# 05_LMS1_Misc.net
KiCad netlist of a schematic drawn in Altium Designer
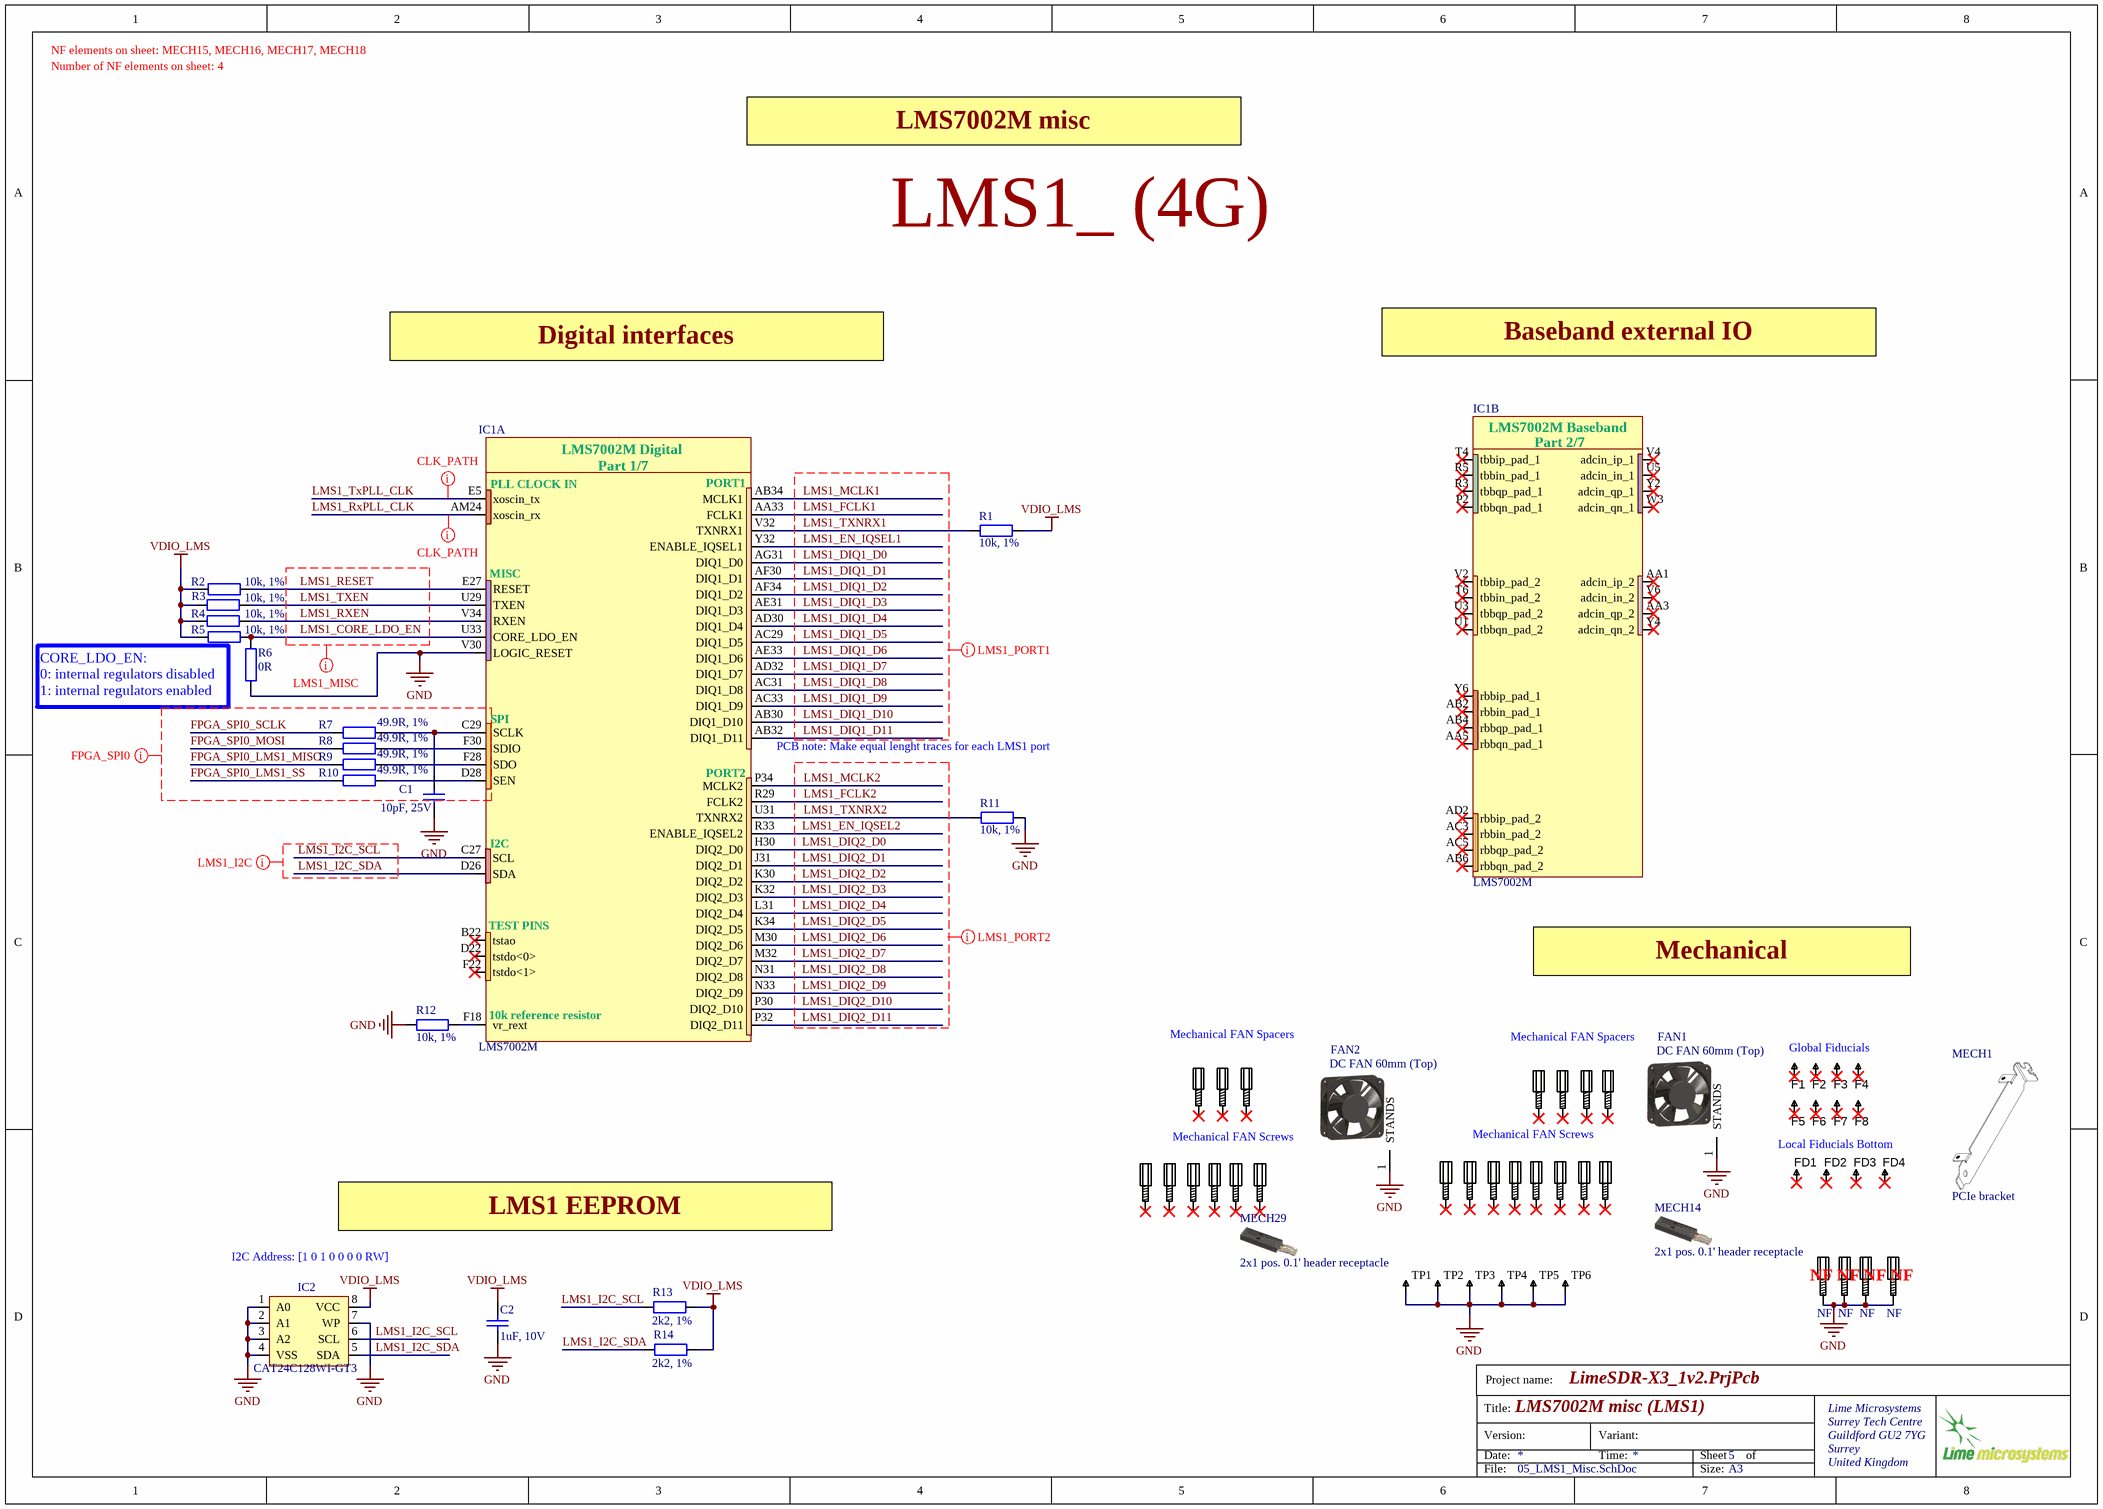
[diagram p0: 05_LMS1_Misc.SchDoc]

(export (version "E")
  (design (tool "Eeschema 10.0.6"))
  (components
    (comp (ref "C1")
      (value "10pF, 25V")
      (footprint "CAP0402")
      (fields (field (name "MANUFACTURER") "AVX"))
      (libsource (lib "LimeMicroAltiumLib_schLib") (part "Cap_0402"))
    )
    (comp (ref "C2")
      (value "1uF, 10V")
      (footprint "CAP0402")
      (fields (field (name "MANUFACTURER") "TDK"))
      (libsource (lib "") (part "Cap_0402_1"))
    )
    (comp (ref "F1")
      (value "Fiducial")
      (footprint "Fiducial")
      (libsource (lib "VGTU_Altium_lib") (part "Fiducial"))
    )
    (comp (ref "F2")
      (value "Fiducial")
      (footprint "Fiducial")
      (libsource (lib "VGTU_Altium_lib") (part "Fiducial"))
    )
    (comp (ref "F3")
      (value "Fiducial")
      (footprint "Fiducial")
      (libsource (lib "VGTU_Altium_lib") (part "Fiducial"))
    )
    (comp (ref "F4")
      (value "Fiducial")
      (footprint "Fiducial")
      (libsource (lib "VGTU_Altium_lib") (part "Fiducial"))
    )
    (comp (ref "F5")
      (value "Fiducial")
      (footprint "Fiducial")
      (libsource (lib "VGTU_Altium_lib") (part "Fiducial"))
    )
    (comp (ref "F6")
      (value "Fiducial")
      (footprint "Fiducial")
      (libsource (lib "VGTU_Altium_lib") (part "Fiducial"))
    )
    (comp (ref "F7")
      (value "Fiducial")
      (footprint "Fiducial")
      (libsource (lib "VGTU_Altium_lib") (part "Fiducial"))
    )
    (comp (ref "F8")
      (value "Fiducial")
      (footprint "Fiducial")
      (libsource (lib "VGTU_Altium_lib") (part "Fiducial"))
    )
    (comp (ref "FAN1")
      (value "DC FAN 60mm (Top)")
      (footprint "FAN_60mm")
      (fields (field (name "MANUFACTURER") "Sunon"))
      (libsource (lib "LimeMicroAltiumLib_schLib") (part "12V_DC_FAN"))
    )
    (comp (ref "FAN2")
      (value "DC FAN 60mm (Top)")
      (footprint "FAN_60mm")
      (fields (field (name "MANUFACTURER") "Sunon"))
      (libsource (lib "LimeMicroAltiumLib_schLib") (part "12V_DC_FAN"))
    )
    (comp (ref "FD1")
      (value "Fiducial")
      (footprint "Fiducial_local")
      (libsource (lib "") (part "Fiducial_1"))
    )
    (comp (ref "FD2")
      (value "Fiducial")
      (footprint "Fiducial_local")
      (libsource (lib "LimeMicroAltiumLib_schLib") (part "Fiducial"))
    )
    (comp (ref "FD3")
      (value "Fiducial")
      (footprint "Fiducial_local")
      (libsource (lib "") (part "Fiducial_2"))
    )
    (comp (ref "FD4")
      (value "Fiducial")
      (footprint "Fiducial_local")
      (libsource (lib "LimeMicroAltiumLib_schLib") (part "Fiducial"))
    )
    (comp (ref "IC1")
      (value "LMS7002M")
      (footprint "LMS7002M_v5")
      (description "Schematic symbol revision 4. Default footprint - 0.31mm pad")
      (fields (field (name "MANUFACTURER") "Lime Microsystems"))
      (libsource (lib "LimeMicroAltiumLib_schLib_r04") (part "LMS7002Mr4"))
    )
    (comp (ref "IC2")
      (value "CAT24C128WI-GT3")
      (footprint "SOIC127P600-8DL_v2")
      (fields (field (name "MANUFACTURER") "ON Semiconductor") (field (name "BASE PART NUMBER") "CAT24C128"))
      (libsource (lib "LimeMicroAltiumLib_schLib") (part "24FC64F"))
    )
    (comp (ref "MECH1")
      (value "PCIe bracket")
      (footprint "PCIe_bracket")
      (fields (field (name "MANUFACTURER") "Keystone Electronics"))
      (libsource (lib "LimeMicroAltiumLib_schLib_r01") (part "PCIe_bracket"))
    )
    (comp (ref "MECH2")
      (value "Spacer M3")
      (description "STANDOFF M/F MET 5MM HEX 10MM L")
      (fields (field (name "MANUFACTURER") "BOSSARD"))
      (libsource (lib "LimeMicroAltiumLib_schLib") (part "STANDOFF_M-F_THREADED_M3x8x10mm_HEX_5mm dia"))
    )
    (comp (ref "MECH3")
      (value "Spacer M3")
      (description "STANDOFF M/F MET 5MM HEX 10MM L")
      (fields (field (name "MANUFACTURER") "BOSSARD"))
      (libsource (lib "LimeMicroAltiumLib_schLib") (part "STANDOFF_M-F_THREADED_M3x8x10mm_HEX_5mm dia"))
    )
    (comp (ref "MECH4")
      (value "Spacer M3")
      (description "STANDOFF M/F MET 5MM HEX 10MM L")
      (fields (field (name "MANUFACTURER") "BOSSARD"))
      (libsource (lib "LimeMicroAltiumLib_schLib") (part "STANDOFF_M-F_THREADED_M3x8x10mm_HEX_5mm dia"))
    )
    (comp (ref "MECH5")
      (value "Spacer M3")
      (description "STANDOFF M/F MET 5MM HEX 10MM L")
      (fields (field (name "MANUFACTURER") "BOSSARD"))
      (libsource (lib "LimeMicroAltiumLib_schLib") (part "STANDOFF_M-F_THREADED_M3x8x10mm_HEX_5mm dia"))
    )
    (comp (ref "MECH6")
      (value "Screws M3")
      (description "STANDOFF M/F MET 5MM HEX 10MM L")
      (fields (field (name "MANUFACTURER") "BOSSARD"))
      (libsource (lib "") (part "STANDOFF_M-F_THREADED_M3x8x10mm_HEX_5mm dia_1"))
    )
    (comp (ref "MECH7")
      (value "Screws M3")
      (description "STANDOFF M/F MET 5MM HEX 10MM L")
      (fields (field (name "MANUFACTURER") "BOSSARD"))
      (libsource (lib "") (part "STANDOFF_M-F_THREADED_M3x8x10mm_HEX_5mm dia_1"))
    )
    (comp (ref "MECH8")
      (value "Screws M3")
      (description "STANDOFF M/F MET 5MM HEX 10MM L")
      (fields (field (name "MANUFACTURER") "BOSSARD"))
      (libsource (lib "") (part "STANDOFF_M-F_THREADED_M3x8x10mm_HEX_5mm dia_1"))
    )
    (comp (ref "MECH9")
      (value "Screws M3")
      (description "STANDOFF M/F MET 5MM HEX 10MM L")
      (fields (field (name "MANUFACTURER") "BOSSARD"))
      (libsource (lib "") (part "STANDOFF_M-F_THREADED_M3x8x10mm_HEX_5mm dia_1"))
    )
    (comp (ref "MECH10")
      (value "Screws M3")
      (description "STANDOFF M/F MET 5MM HEX 10MM L")
      (fields (field (name "MANUFACTURER") "BOSSARD"))
      (libsource (lib "") (part "STANDOFF_M-F_THREADED_M3x8x10mm_HEX_5mm dia_1"))
    )
    (comp (ref "MECH11")
      (value "Screws M3")
      (description "STANDOFF M/F MET 5MM HEX 10MM L")
      (fields (field (name "MANUFACTURER") "BOSSARD"))
      (libsource (lib "") (part "STANDOFF_M-F_THREADED_M3x8x10mm_HEX_5mm dia_1"))
    )
    (comp (ref "MECH12")
      (value "Screws M3")
      (description "STANDOFF M/F MET 5MM HEX 10MM L")
      (fields (field (name "MANUFACTURER") "BOSSARD"))
      (libsource (lib "") (part "STANDOFF_M-F_THREADED_M3x8x10mm_HEX_5mm dia_1"))
    )
    (comp (ref "MECH13")
      (value "Screws M3")
      (description "STANDOFF M/F MET 5MM HEX 10MM L")
      (fields (field (name "MANUFACTURER") "BOSSARD"))
      (libsource (lib "") (part "STANDOFF_M-F_THREADED_M3x8x10mm_HEX_5mm dia_1"))
    )
    (comp (ref "MECH14")
      (value "2x1 pos. 0.1' header receptacle")
      (fields (field (name "MANUFACTURER") "Molex"))
      (libsource (lib "LimeMicroAltiumLib_schLib_r01") (part "Header_1x2_receptacle"))
    )
    (comp (ref "MECH15")
      (value "Standoff")
      (footprint "PCB_standoff")
      (description "STANDOFF M/F MET 5MM HEX 10MM L")
      (fields (field (name "MANUFACTURER") "FIX&FASTEN") (field (name "ASSEMBLY INFO") "NF"))
      (libsource (lib "") (part "STANDOFF_M-F_THREADED_M3x8x10mm_HEX_5mm dia_1"))
    )
    (comp (ref "MECH16")
      (value "Standoff")
      (footprint "PCB_standoff")
      (description "STANDOFF M/F MET 5MM HEX 10MM L")
      (fields (field (name "MANUFACTURER") "FIX&FASTEN") (field (name "ASSEMBLY INFO") "NF"))
      (libsource (lib "") (part "STANDOFF_M-F_THREADED_M3x8x10mm_HEX_5mm dia_1"))
    )
    (comp (ref "MECH17")
      (value "Standoff")
      (footprint "PCB_standoff")
      (description "STANDOFF M/F MET 5MM HEX 10MM L")
      (fields (field (name "MANUFACTURER") "FIX&FASTEN") (field (name "ASSEMBLY INFO") "NF"))
      (libsource (lib "") (part "STANDOFF_M-F_THREADED_M3x8x10mm_HEX_5mm dia_1"))
    )
    (comp (ref "MECH18")
      (value "Standoff")
      (footprint "PCB_standoff")
      (description "STANDOFF M/F MET 5MM HEX 10MM L")
      (fields (field (name "MANUFACTURER") "FIX&FASTEN") (field (name "ASSEMBLY INFO") "NF"))
      (libsource (lib "") (part "STANDOFF_M-F_THREADED_M3x8x10mm_HEX_5mm dia_2"))
    )
    (comp (ref "MECH20")
      (value "Spacer M3")
      (description "STANDOFF M/F MET 5MM HEX 10MM L")
      (fields (field (name "MANUFACTURER") "BOSSARD"))
      (libsource (lib "LimeMicroAltiumLib_schLib") (part "STANDOFF_M-F_THREADED_M3x8x10mm_HEX_5mm dia"))
    )
    (comp (ref "MECH21")
      (value "Spacer M3")
      (description "STANDOFF M/F MET 5MM HEX 10MM L")
      (fields (field (name "MANUFACTURER") "BOSSARD"))
      (libsource (lib "LimeMicroAltiumLib_schLib") (part "STANDOFF_M-F_THREADED_M3x8x10mm_HEX_5mm dia"))
    )
    (comp (ref "MECH22")
      (value "Spacer M3")
      (description "STANDOFF M/F MET 5MM HEX 10MM L")
      (fields (field (name "MANUFACTURER") "BOSSARD"))
      (libsource (lib "LimeMicroAltiumLib_schLib") (part "STANDOFF_M-F_THREADED_M3x8x10mm_HEX_5mm dia"))
    )
    (comp (ref "MECH23")
      (value "Screws M3")
      (description "STANDOFF M/F MET 5MM HEX 10MM L")
      (fields (field (name "MANUFACTURER") "BOSSARD"))
      (libsource (lib "") (part "STANDOFF_M-F_THREADED_M3x8x10mm_HEX_5mm dia_1"))
    )
    (comp (ref "MECH24")
      (value "Screws M3")
      (description "STANDOFF M/F MET 5MM HEX 10MM L")
      (fields (field (name "MANUFACTURER") "BOSSARD"))
      (libsource (lib "") (part "STANDOFF_M-F_THREADED_M3x8x10mm_HEX_5mm dia_1"))
    )
    (comp (ref "MECH25")
      (value "Screws M3")
      (description "STANDOFF M/F MET 5MM HEX 10MM L")
      (fields (field (name "MANUFACTURER") "BOSSARD"))
      (libsource (lib "") (part "STANDOFF_M-F_THREADED_M3x8x10mm_HEX_5mm dia_1"))
    )
    (comp (ref "MECH26")
      (value "Screws M3")
      (description "STANDOFF M/F MET 5MM HEX 10MM L")
      (fields (field (name "MANUFACTURER") "BOSSARD"))
      (libsource (lib "") (part "STANDOFF_M-F_THREADED_M3x8x10mm_HEX_5mm dia_1"))
    )
    (comp (ref "MECH27")
      (value "Screws M3")
      (description "STANDOFF M/F MET 5MM HEX 10MM L")
      (fields (field (name "MANUFACTURER") "BOSSARD"))
      (libsource (lib "") (part "STANDOFF_M-F_THREADED_M3x8x10mm_HEX_5mm dia_1"))
    )
    (comp (ref "MECH28")
      (value "Screws M3")
      (description "STANDOFF M/F MET 5MM HEX 10MM L")
      (fields (field (name "MANUFACTURER") "BOSSARD"))
      (libsource (lib "") (part "STANDOFF_M-F_THREADED_M3x8x10mm_HEX_5mm dia_1"))
    )
    (comp (ref "MECH29")
      (value "2x1 pos. 0.1' header receptacle")
      (fields (field (name "MANUFACTURER") "Molex"))
      (libsource (lib "LimeMicroAltiumLib_schLib_r01") (part "Header_1x2_receptacle"))
    )
    (comp (ref "R1")
      (value "10k, 1%")
      (footprint "RES0402")
      (fields (field (name "MANUFACTURER") "Yageo") (field (name "TOLERANCE") "±1%"))
      (libsource (lib "LimeMicroAltiumLib_schLib") (part "Res_0402"))
    )
    (comp (ref "R2")
      (value "10k, 1%")
      (footprint "RES0402")
      (fields (field (name "MANUFACTURER") "Yageo") (field (name "TOLERANCE") "±1%"))
      (libsource (lib "LimeMicroAltiumLib_schLib") (part "Res_0402"))
    )
    (comp (ref "R3")
      (value "10k, 1%")
      (footprint "RES0402")
      (fields (field (name "MANUFACTURER") "Yageo") (field (name "TOLERANCE") "±1%"))
      (libsource (lib "LimeMicroAltiumLib_schLib") (part "Res_0402"))
    )
    (comp (ref "R4")
      (value "10k, 1%")
      (footprint "RES0402")
      (fields (field (name "MANUFACTURER") "Yageo") (field (name "TOLERANCE") "±1%"))
      (libsource (lib "LimeMicroAltiumLib_schLib") (part "Res_0402"))
    )
    (comp (ref "R5")
      (value "10k, 1%")
      (footprint "RES0402")
      (fields (field (name "MANUFACTURER") "Yageo") (field (name "TOLERANCE") "±1%"))
      (libsource (lib "LimeMicroAltiumLib_schLib") (part "Res_0402"))
    )
    (comp (ref "R6")
      (value "0R")
      (footprint "RES0402")
      (fields (field (name "MANUFACTURER") "Yageo") (field (name "TOLERANCE") "Jumper"))
      (libsource (lib "LimeMicroAltiumLib_schLib") (part "Res_0402"))
    )
    (comp (ref "R7")
      (value "49.9R, 1%")
      (footprint "RES0402")
      (fields
        (field (name "TOLERANCE") "±1%")
        (field (name "MANUFACTURER") "Samsung Electro-Mechanics America, Inc.")
        (field (name "MANUFACTURER PART NUMBER") "RC1005F49R9CS")
      )
      (libsource (lib "LimeMicroAltiumLib_schLib") (part "Res_0402"))
    )
    (comp (ref "R8")
      (value "49.9R, 1%")
      (footprint "RES0402")
      (fields
        (field (name "TOLERANCE") "±1%")
        (field (name "MANUFACTURER") "Samsung Electro-Mechanics America, Inc.")
        (field (name "MANUFACTURER PART NUMBER") "RC1005F49R9CS")
      )
      (libsource (lib "LimeMicroAltiumLib_schLib") (part "Res_0402"))
    )
    (comp (ref "R9")
      (value "49.9R, 1%")
      (footprint "RES0402")
      (fields
        (field (name "TOLERANCE") "±1%")
        (field (name "MANUFACTURER") "Samsung Electro-Mechanics America, Inc.")
        (field (name "MANUFACTURER PART NUMBER") "RC1005F49R9CS")
      )
      (libsource (lib "LimeMicroAltiumLib_schLib") (part "Res_0402"))
    )
    (comp (ref "R10")
      (value "49.9R, 1%")
      (footprint "RES0402")
      (fields
        (field (name "TOLERANCE") "±1%")
        (field (name "MANUFACTURER") "Samsung Electro-Mechanics America, Inc.")
        (field (name "MANUFACTURER PART NUMBER") "RC1005F49R9CS")
      )
      (libsource (lib "LimeMicroAltiumLib_schLib") (part "Res_0402"))
    )
    (comp (ref "R11")
      (value "10k, 1%")
      (footprint "RES0402")
      (fields (field (name "MANUFACTURER") "Yageo") (field (name "TOLERANCE") "±1%"))
      (libsource (lib "LimeMicroAltiumLib_schLib") (part "Res_0402"))
    )
    (comp (ref "R12")
      (value "10k, 1%")
      (footprint "RES0402")
      (fields (field (name "MANUFACTURER") "Yageo") (field (name "TOLERANCE") "±1%"))
      (libsource (lib "") (part "Res_0402_1"))
    )
    (comp (ref "R13")
      (value "2k2, 1%")
      (footprint "RES0402")
      (fields (field (name "MANUFACTURER") "Stackpole Electronics Inc") (field (name "TOLERANCE") "±1%"))
      (libsource (lib "LimeMicroAltiumLib_schLib") (part "Res_0402"))
    )
    (comp (ref "R14")
      (value "2k2, 1%")
      (footprint "RES0402")
      (fields (field (name "MANUFACTURER") "Stackpole Electronics Inc") (field (name "TOLERANCE") "±1%"))
      (libsource (lib "LimeMicroAltiumLib_schLib") (part "Res_0402"))
    )
    (comp (ref "TP1")
      (value "TESTPOINT_THT_MINI")
      (footprint "TP-SMD-LOW_PROFILE")
      (description "Test Point PCB mount Miniature White")
      (fields (field (name "MANUFACTURER") "Harwin Inc"))
      (libsource (lib "LimeMicroAltiumLib_schLib") (part "TESTPOINT_THT_MINI"))
    )
    (comp (ref "TP2")
      (value "TESTPOINT_THT_MINI")
      (footprint "TP-SMD-LOW_PROFILE")
      (description "Test Point PCB mount Miniature White")
      (fields (field (name "MANUFACTURER") "Harwin Inc"))
      (libsource (lib "LimeMicroAltiumLib_schLib") (part "TESTPOINT_THT_MINI"))
    )
    (comp (ref "TP3")
      (value "TESTPOINT_THT_MINI")
      (footprint "TP-SMD-LOW_PROFILE")
      (description "Test Point PCB mount Miniature White")
      (fields (field (name "MANUFACTURER") "Harwin Inc"))
      (libsource (lib "LimeMicroAltiumLib_schLib") (part "TESTPOINT_THT_MINI"))
    )
    (comp (ref "TP4")
      (value "TESTPOINT_THT_MINI")
      (footprint "TP-SMD-LOW_PROFILE")
      (description "Test Point PCB mount Miniature White")
      (fields (field (name "MANUFACTURER") "Harwin Inc"))
      (libsource (lib "LimeMicroAltiumLib_schLib") (part "TESTPOINT_THT_MINI"))
    )
    (comp (ref "TP5")
      (value "TESTPOINT_THT_MINI")
      (footprint "TP-SMD-LOW_PROFILE")
      (description "Test Point PCB mount Miniature White")
      (fields (field (name "MANUFACTURER") "Harwin Inc"))
      (libsource (lib "LimeMicroAltiumLib_schLib") (part "TESTPOINT_THT_MINI"))
    )
    (comp (ref "TP6")
      (value "TESTPOINT_THT_MINI")
      (footprint "TP-SMD-LOW_PROFILE")
      (description "Test Point PCB mount Miniature White")
      (fields (field (name "MANUFACTURER") "Harwin Inc"))
      (libsource (lib "LimeMicroAltiumLib_schLib") (part "TESTPOINT_THT_MINI"))
    )
  )
  (nets
    (net (code "1") (name "/FPGA_SPI0_LMS1_MISO") (class "Default")
      (node (ref "R9") (pin "2") (pinfunction "2_2") (pintype "passive"))
    )
    (net (code "2") (name "/FPGA_SPI0_LMS1_SS") (class "Default")
      (node (ref "R10") (pin "2") (pinfunction "2_2") (pintype "passive"))
    )
    (net (code "3") (name "/FPGA_SPI0_MOSI") (class "Default")
      (node (ref "R8") (pin "2") (pinfunction "2_2") (pintype "passive"))
    )
    (net (code "4") (name "/FPGA_SPI0_SCLK") (class "Default")
      (node (ref "R7") (pin "2") (pinfunction "2_2") (pintype "passive"))
    )
    (net (code "5") (name "/LMS1_CORE_LDO_EN") (class "Default")
      (node (ref "IC1") (pin "U33") (pinfunction "CORE_LDO_EN_U33") (pintype "passive"))
      (node (ref "R5") (pin "1") (pinfunction "1_1") (pintype "passive"))
      (node (ref "R6") (pin "2") (pinfunction "2_2") (pintype "passive"))
    )
    (net (code "6") (name "/LMS1_DIQ1_D0") (class "Default")
      (node (ref "IC1") (pin "AG31") (pinfunction "DIQ1_D0_AG31") (pintype "passive"))
    )
    (net (code "7") (name "/LMS1_DIQ1_D1") (class "Default")
      (node (ref "IC1") (pin "AF30") (pinfunction "DIQ1_D1_AF30") (pintype "passive"))
    )
    (net (code "8") (name "/LMS1_DIQ1_D2") (class "Default")
      (node (ref "IC1") (pin "AF34") (pinfunction "DIQ1_D2_AF34") (pintype "passive"))
    )
    (net (code "9") (name "/LMS1_DIQ1_D3") (class "Default")
      (node (ref "IC1") (pin "AE31") (pinfunction "DIQ1_D3_AE31") (pintype "passive"))
    )
    (net (code "10") (name "/LMS1_DIQ1_D4") (class "Default")
      (node (ref "IC1") (pin "AD30") (pinfunction "DIQ1_D4_AD30") (pintype "passive"))
    )
    (net (code "11") (name "/LMS1_DIQ1_D5") (class "Default")
      (node (ref "IC1") (pin "AC29") (pinfunction "DIQ1_D5_AC29") (pintype "passive"))
    )
    (net (code "12") (name "/LMS1_DIQ1_D6") (class "Default")
      (node (ref "IC1") (pin "AE33") (pinfunction "DIQ1_D6_AE33") (pintype "passive"))
    )
    (net (code "13") (name "/LMS1_DIQ1_D7") (class "Default")
      (node (ref "IC1") (pin "AD32") (pinfunction "DIQ1_D7_AD32") (pintype "passive"))
    )
    (net (code "14") (name "/LMS1_DIQ1_D8") (class "Default")
      (node (ref "IC1") (pin "AC31") (pinfunction "DIQ1_D8_AC31") (pintype "passive"))
    )
    (net (code "15") (name "/LMS1_DIQ1_D9") (class "Default")
      (node (ref "IC1") (pin "AC33") (pinfunction "DIQ1_D9_AC33") (pintype "passive"))
    )
    (net (code "16") (name "/LMS1_DIQ1_D10") (class "Default")
      (node (ref "IC1") (pin "AB30") (pinfunction "DIQ1_D10_AB30") (pintype "passive"))
    )
    (net (code "17") (name "/LMS1_DIQ1_D11") (class "Default")
      (node (ref "IC1") (pin "AB32") (pinfunction "DIQ1_D11_AB32") (pintype "passive"))
    )
    (net (code "18") (name "/LMS1_DIQ2_D0") (class "Default")
      (node (ref "IC1") (pin "H30") (pinfunction "DIQ2_D0_H30") (pintype "passive"))
    )
    (net (code "19") (name "/LMS1_DIQ2_D1") (class "Default")
      (node (ref "IC1") (pin "J31") (pinfunction "DIQ2_D1_J31") (pintype "passive"))
    )
    (net (code "20") (name "/LMS1_DIQ2_D2") (class "Default")
      (node (ref "IC1") (pin "K30") (pinfunction "DIQ2_D2_K30") (pintype "passive"))
    )
    (net (code "21") (name "/LMS1_DIQ2_D3") (class "Default")
      (node (ref "IC1") (pin "K32") (pinfunction "DIQ2_D3_K32") (pintype "passive"))
    )
    (net (code "22") (name "/LMS1_DIQ2_D4") (class "Default")
      (node (ref "IC1") (pin "L31") (pinfunction "DIQ2_D4_L31") (pintype "passive"))
    )
    (net (code "23") (name "/LMS1_DIQ2_D5") (class "Default")
      (node (ref "IC1") (pin "K34") (pinfunction "DIQ2_D5_K34") (pintype "passive"))
    )
    (net (code "24") (name "/LMS1_DIQ2_D6") (class "Default")
      (node (ref "IC1") (pin "M30") (pinfunction "DIQ2_D6_M30") (pintype "passive"))
    )
    (net (code "25") (name "/LMS1_DIQ2_D7") (class "Default")
      (node (ref "IC1") (pin "M32") (pinfunction "DIQ2_D7_M32") (pintype "passive"))
    )
    (net (code "26") (name "/LMS1_DIQ2_D8") (class "Default")
      (node (ref "IC1") (pin "N31") (pinfunction "DIQ2_D8_N31") (pintype "passive"))
    )
    (net (code "27") (name "/LMS1_DIQ2_D9") (class "Default")
      (node (ref "IC1") (pin "N33") (pinfunction "DIQ2_D9_N33") (pintype "passive"))
    )
    (net (code "28") (name "/LMS1_DIQ2_D10") (class "Default")
      (node (ref "IC1") (pin "P30") (pinfunction "DIQ2_D10_P30") (pintype "passive"))
    )
    (net (code "29") (name "/LMS1_DIQ2_D11") (class "Default")
      (node (ref "IC1") (pin "P32") (pinfunction "DIQ2_D11_P32") (pintype "passive"))
    )
    (net (code "30") (name "/LMS1_EN_IQSEL1") (class "Default")
      (node (ref "IC1") (pin "Y32") (pinfunction "ENABLE_IQSEL1_Y32") (pintype "passive"))
    )
    (net (code "31") (name "/LMS1_EN_IQSEL2") (class "Default")
      (node (ref "IC1") (pin "R33") (pinfunction "ENABLE_IQSEL2_R33") (pintype "passive"))
    )
    (net (code "32") (name "/LMS1_FCLK1") (class "Default")
      (node (ref "IC1") (pin "AA33") (pinfunction "FCLK1_AA33") (pintype "passive"))
    )
    (net (code "33") (name "/LMS1_FCLK2") (class "Default")
      (node (ref "IC1") (pin "R29") (pinfunction "FCLK2_R29") (pintype "passive"))
    )
    (net (code "34") (name "/LMS1_I2C_SCL") (class "Default")
      (node (ref "IC1") (pin "C27") (pinfunction "SCL_C27") (pintype "passive"))
      (node (ref "IC2") (pin "6") (pinfunction "SCL_6") (pintype "passive"))
      (node (ref "R13") (pin "2") (pinfunction "2_2") (pintype "passive"))
    )
    (net (code "35") (name "/LMS1_I2C_SDA") (class "Default")
      (node (ref "IC1") (pin "D26") (pinfunction "SDA_D26") (pintype "passive"))
      (node (ref "IC2") (pin "5") (pinfunction "SDA_5") (pintype "passive"))
      (node (ref "R14") (pin "2") (pinfunction "2_2") (pintype "passive"))
    )
    (net (code "36") (name "/LMS1_MCLK1") (class "Default")
      (node (ref "IC1") (pin "AB34") (pinfunction "MCLK1_AB34") (pintype "passive"))
    )
    (net (code "37") (name "/LMS1_MCLK2") (class "Default")
      (node (ref "IC1") (pin "P34") (pinfunction "MCLK2_P34") (pintype "passive"))
    )
    (net (code "38") (name "/LMS1_RESET") (class "Default")
      (node (ref "IC1") (pin "E27") (pinfunction "RESET_E27") (pintype "passive"))
      (node (ref "R2") (pin "1") (pinfunction "1_1") (pintype "passive"))
    )
    (net (code "39") (name "/LMS1_RXEN") (class "Default")
      (node (ref "IC1") (pin "V34") (pinfunction "RXEN_V34") (pintype "passive"))
      (node (ref "R4") (pin "2") (pinfunction "2_2") (pintype "passive"))
    )
    (net (code "40") (name "/LMS1_RxPLL_CLK") (class "Default")
      (node (ref "IC1") (pin "AM24") (pinfunction "xoscin_rx_AM24") (pintype "passive"))
    )
    (net (code "41") (name "/LMS1_TXEN") (class "Default")
      (node (ref "IC1") (pin "U29") (pinfunction "TXEN_U29") (pintype "passive"))
      (node (ref "R3") (pin "2") (pinfunction "2_2") (pintype "passive"))
    )
    (net (code "42") (name "/LMS1_TXNRX1") (class "Default")
      (node (ref "IC1") (pin "V32") (pinfunction "TXNRX1_V32") (pintype "passive"))
      (node (ref "R1") (pin "1") (pinfunction "1_1") (pintype "passive"))
    )
    (net (code "43") (name "/LMS1_TXNRX2") (class "Default")
      (node (ref "IC1") (pin "U31") (pinfunction "TXNRX2_U31") (pintype "passive"))
      (node (ref "R11") (pin "2") (pinfunction "2_2") (pintype "passive"))
    )
    (net (code "44") (name "/LMS1_TxPLL_CLK") (class "Default")
      (node (ref "IC1") (pin "E5") (pinfunction "xoscin_tx_E5") (pintype "passive"))
    )
    (net (code "45") (name "GND") (class "Default")
      (node (ref "C1") (pin "2") (pinfunction "2_2") (pintype "passive"))
      (node (ref "C2") (pin "2") (pinfunction "2_2") (pintype "passive"))
      (node (ref "FAN1") (pin "1") (pinfunction "STANDS_1") (pintype "passive"))
      (node (ref "FAN2") (pin "1") (pinfunction "STANDS_1") (pintype "passive"))
      (node (ref "IC1") (pin "V30") (pinfunction "LOGIC_RESET_V30") (pintype "passive"))
      (node (ref "IC2") (pin "1") (pinfunction "A0_1") (pintype "passive"))
      (node (ref "IC2") (pin "2") (pinfunction "A1_2") (pintype "passive"))
      (node (ref "IC2") (pin "3") (pinfunction "A2_3") (pintype "passive"))
      (node (ref "IC2") (pin "4") (pinfunction "VSS_4") (pintype "passive"))
      (node (ref "IC2") (pin "7") (pinfunction "WP_7") (pintype "passive"))
      (node (ref "MECH15") (pin "MH1") (pinfunction "MH1_MH1") (pintype "passive"))
      (node (ref "MECH16") (pin "MH1") (pinfunction "MH1_MH1") (pintype "passive"))
      (node (ref "MECH17") (pin "MH1") (pinfunction "MH1_MH1") (pintype "passive"))
      (node (ref "MECH18") (pin "MH1") (pinfunction "MH1_MH1") (pintype "passive"))
      (node (ref "R11") (pin "1") (pinfunction "1_1") (pintype "passive"))
      (node (ref "R12") (pin "2") (pinfunction "2_2") (pintype "passive"))
      (node (ref "R6") (pin "1") (pinfunction "1_1") (pintype "passive"))
      (node (ref "TP1") (pin "1") (pintype "passive"))
      (node (ref "TP2") (pin "1") (pintype "passive"))
      (node (ref "TP3") (pin "1") (pintype "passive"))
      (node (ref "TP4") (pin "1") (pintype "passive"))
      (node (ref "TP5") (pin "1") (pintype "passive"))
      (node (ref "TP6") (pin "1") (pintype "passive"))
    )
    (net (code "46") (name "Net-(IC1A-SCLK)") (class "Default")
      (node (ref "C1") (pin "1") (pinfunction "1_1") (pintype "passive"))
      (node (ref "IC1") (pin "C29") (pinfunction "SCLK_C29") (pintype "passive"))
      (node (ref "R7") (pin "1") (pinfunction "1_1") (pintype "passive"))
    )
    (net (code "47") (name "Net-(IC1A-SDIO)") (class "Default")
      (node (ref "IC1") (pin "F30") (pinfunction "SDIO_F30") (pintype "passive"))
      (node (ref "R8") (pin "1") (pinfunction "1_1") (pintype "passive"))
    )
    (net (code "48") (name "Net-(IC1A-SDO)") (class "Default")
      (node (ref "IC1") (pin "F28") (pinfunction "SDO_F28") (pintype "passive"))
      (node (ref "R9") (pin "1") (pinfunction "1_1") (pintype "passive"))
    )
    (net (code "49") (name "Net-(IC1A-SEN)") (class "Default")
      (node (ref "IC1") (pin "D28") (pinfunction "SEN_D28") (pintype "passive"))
      (node (ref "R10") (pin "1") (pinfunction "1_1") (pintype "passive"))
    )
    (net (code "50") (name "Net-(IC1A-vr_rext)") (class "Default")
      (node (ref "IC1") (pin "F18") (pinfunction "vr_rext_F18") (pintype "passive"))
      (node (ref "R12") (pin "1") (pinfunction "1_1") (pintype "passive"))
    )
    (net (code "51") (name "VDIO_LMS") (class "Default")
      (node (ref "C2") (pin "1") (pinfunction "1_1") (pintype "passive"))
      (node (ref "IC2") (pin "8") (pinfunction "VCC_8") (pintype "passive"))
      (node (ref "R1") (pin "2") (pinfunction "2_2") (pintype "passive"))
      (node (ref "R13") (pin "1") (pinfunction "1_1") (pintype "passive"))
      (node (ref "R14") (pin "1") (pinfunction "1_1") (pintype "passive"))
      (node (ref "R2") (pin "2") (pinfunction "2_2") (pintype "passive"))
      (node (ref "R3") (pin "1") (pinfunction "1_1") (pintype "passive"))
      (node (ref "R4") (pin "1") (pinfunction "1_1") (pintype "passive"))
      (node (ref "R5") (pin "2") (pinfunction "2_2") (pintype "passive"))
    )
    (net (code "52") (name "unconnected-(F1-Pad1)") (class "Default")
      (node (ref "F1") (pin "1") (pintype "passive+no_connect"))
    )
    (net (code "53") (name "unconnected-(F2-Pad1)") (class "Default")
      (node (ref "F2") (pin "1") (pintype "passive+no_connect"))
    )
    (net (code "54") (name "unconnected-(F3-Pad1)") (class "Default")
      (node (ref "F3") (pin "1") (pintype "passive+no_connect"))
    )
    (net (code "55") (name "unconnected-(F4-Pad1)") (class "Default")
      (node (ref "F4") (pin "1") (pintype "passive+no_connect"))
    )
    (net (code "56") (name "unconnected-(F5-Pad1)") (class "Default")
      (node (ref "F5") (pin "1") (pintype "passive+no_connect"))
    )
    (net (code "57") (name "unconnected-(F6-Pad1)") (class "Default")
      (node (ref "F6") (pin "1") (pintype "passive+no_connect"))
    )
    (net (code "58") (name "unconnected-(F7-Pad1)") (class "Default")
      (node (ref "F7") (pin "1") (pintype "passive+no_connect"))
    )
    (net (code "59") (name "unconnected-(F8-Pad1)") (class "Default")
      (node (ref "F8") (pin "1") (pintype "passive+no_connect"))
    )
    (net (code "60") (name "unconnected-(FD1-Pad1)") (class "Default")
      (node (ref "FD1") (pin "1") (pintype "passive+no_connect"))
    )
    (net (code "61") (name "unconnected-(FD2-Pad1)") (class "Default")
      (node (ref "FD2") (pin "1") (pintype "passive+no_connect"))
    )
    (net (code "62") (name "unconnected-(FD3-Pad1)") (class "Default")
      (node (ref "FD3") (pin "1") (pintype "passive+no_connect"))
    )
    (net (code "63") (name "unconnected-(FD4-Pad1)") (class "Default")
      (node (ref "FD4") (pin "1") (pintype "passive+no_connect"))
    )
    (net (code "64") (name "unconnected-(IC1A-tstao-PadB22)") (class "Default")
      (node (ref "IC1") (pin "B22") (pinfunction "tstao_B22") (pintype "passive"))
    )
    (net (code "65") (name "unconnected-(IC1A-tstdo<0>-PadD22)") (class "Default")
      (node (ref "IC1") (pin "D22") (pinfunction "tstdo<0>_D22") (pintype "passive"))
    )
    (net (code "66") (name "unconnected-(IC1A-tstdo<1>-PadF22)") (class "Default")
      (node (ref "IC1") (pin "F22") (pinfunction "tstdo<1>_F22") (pintype "passive"))
    )
    (net (code "67") (name "unconnected-(IC1B-adcin_in_1-PadU5)") (class "Default")
      (node (ref "IC1") (pin "U5") (pinfunction "adcin_in_1_U5") (pintype "passive+no_connect"))
    )
    (net (code "68") (name "unconnected-(IC1B-adcin_in_2-PadV6)") (class "Default")
      (node (ref "IC1") (pin "V6") (pinfunction "adcin_in_2_V6") (pintype "passive+no_connect"))
    )
    (net (code "69") (name "unconnected-(IC1B-adcin_ip_1-PadV4)") (class "Default")
      (node (ref "IC1") (pin "V4") (pinfunction "adcin_ip_1_V4") (pintype "passive+no_connect"))
    )
    (net (code "70") (name "unconnected-(IC1B-adcin_ip_2-PadAA1)") (class "Default")
      (node (ref "IC1") (pin "AA1") (pinfunction "adcin_ip_2_AA1") (pintype "passive+no_connect"))
    )
    (net (code "71") (name "unconnected-(IC1B-adcin_qn_1-PadW3)") (class "Default")
      (node (ref "IC1") (pin "W3") (pinfunction "adcin_qn_1_W3") (pintype "passive+no_connect"))
    )
    (net (code "72") (name "unconnected-(IC1B-adcin_qn_2-PadY4)") (class "Default")
      (node (ref "IC1") (pin "Y4") (pinfunction "adcin_qn_2_Y4") (pintype "passive+no_connect"))
    )
    (net (code "73") (name "unconnected-(IC1B-adcin_qp_1-PadY2)") (class "Default")
      (node (ref "IC1") (pin "Y2") (pinfunction "adcin_qp_1_Y2") (pintype "passive+no_connect"))
    )
    (net (code "74") (name "unconnected-(IC1B-adcin_qp_2-PadAA3)") (class "Default")
      (node (ref "IC1") (pin "AA3") (pinfunction "adcin_qp_2_AA3") (pintype "passive+no_connect"))
    )
    (net (code "75") (name "unconnected-(IC1B-rbbin_pad_1-PadAB2)") (class "Default")
      (node (ref "IC1") (pin "AB2") (pinfunction "rbbin_pad_1_AB2") (pintype "passive+no_connect"))
    )
    (net (code "76") (name "unconnected-(IC1B-rbbin_pad_2-PadAC3)") (class "Default")
      (node (ref "IC1") (pin "AC3") (pinfunction "rbbin_pad_2_AC3") (pintype "passive+no_connect"))
    )
    (net (code "77") (name "unconnected-(IC1B-rbbip_pad_1-PadY6)") (class "Default")
      (node (ref "IC1") (pin "Y6") (pinfunction "rbbip_pad_1_Y6") (pintype "passive+no_connect"))
    )
    (net (code "78") (name "unconnected-(IC1B-rbbip_pad_2-PadAD2)") (class "Default")
      (node (ref "IC1") (pin "AD2") (pinfunction "rbbip_pad_2_AD2") (pintype "passive+no_connect"))
    )
    (net (code "79") (name "unconnected-(IC1B-rbbqn_pad_1-PadAA5)") (class "Default")
      (node (ref "IC1") (pin "AA5") (pinfunction "rbbqn_pad_1_AA5") (pintype "passive+no_connect"))
    )
    (net (code "80") (name "unconnected-(IC1B-rbbqn_pad_2-PadAB6)") (class "Default")
      (node (ref "IC1") (pin "AB6") (pinfunction "rbbqn_pad_2_AB6") (pintype "passive+no_connect"))
    )
    (net (code "81") (name "unconnected-(IC1B-rbbqp_pad_1-PadAB4)") (class "Default")
      (node (ref "IC1") (pin "AB4") (pinfunction "rbbqp_pad_1_AB4") (pintype "passive+no_connect"))
    )
    (net (code "82") (name "unconnected-(IC1B-rbbqp_pad_2-PadAC5)") (class "Default")
      (node (ref "IC1") (pin "AC5") (pinfunction "rbbqp_pad_2_AC5") (pintype "passive+no_connect"))
    )
    (net (code "83") (name "unconnected-(IC1B-tbbin_pad_1-PadR5)") (class "Default")
      (node (ref "IC1") (pin "R5") (pinfunction "tbbin_pad_1_R5") (pintype "passive+no_connect"))
    )
    (net (code "84") (name "unconnected-(IC1B-tbbin_pad_2-PadT6)") (class "Default")
      (node (ref "IC1") (pin "T6") (pinfunction "tbbin_pad_2_T6") (pintype "passive+no_connect"))
    )
    (net (code "85") (name "unconnected-(IC1B-tbbip_pad_1-PadT4)") (class "Default")
      (node (ref "IC1") (pin "T4") (pinfunction "tbbip_pad_1_T4") (pintype "passive+no_connect"))
    )
    (net (code "86") (name "unconnected-(IC1B-tbbip_pad_2-PadV2)") (class "Default")
      (node (ref "IC1") (pin "V2") (pinfunction "tbbip_pad_2_V2") (pintype "passive+no_connect"))
    )
    (net (code "87") (name "unconnected-(IC1B-tbbqn_pad_1-PadP2)") (class "Default")
      (node (ref "IC1") (pin "P2") (pinfunction "tbbqn_pad_1_P2") (pintype "passive+no_connect"))
    )
    (net (code "88") (name "unconnected-(IC1B-tbbqn_pad_2-PadU1)") (class "Default")
      (node (ref "IC1") (pin "U1") (pinfunction "tbbqn_pad_2_U1") (pintype "passive+no_connect"))
    )
    (net (code "89") (name "unconnected-(IC1B-tbbqp_pad_1-PadR3)") (class "Default")
      (node (ref "IC1") (pin "R3") (pinfunction "tbbqp_pad_1_R3") (pintype "passive+no_connect"))
    )
    (net (code "90") (name "unconnected-(IC1B-tbbqp_pad_2-PadU3)") (class "Default")
      (node (ref "IC1") (pin "U3") (pinfunction "tbbqp_pad_2_U3") (pintype "passive+no_connect"))
    )
    (net (code "91") (name "unconnected-(MECH2-PadMH1)") (class "Default")
      (node (ref "MECH2") (pin "MH1") (pinfunction "MH1_MH1") (pintype "passive+no_connect"))
    )
    (net (code "92") (name "unconnected-(MECH3-PadMH1)") (class "Default")
      (node (ref "MECH3") (pin "MH1") (pinfunction "MH1_MH1") (pintype "passive+no_connect"))
    )
    (net (code "93") (name "unconnected-(MECH4-PadMH1)") (class "Default")
      (node (ref "MECH4") (pin "MH1") (pinfunction "MH1_MH1") (pintype "passive+no_connect"))
    )
    (net (code "94") (name "unconnected-(MECH5-PadMH1)") (class "Default")
      (node (ref "MECH5") (pin "MH1") (pinfunction "MH1_MH1") (pintype "passive+no_connect"))
    )
    (net (code "95") (name "unconnected-(MECH6-PadMH1)") (class "Default")
      (node (ref "MECH6") (pin "MH1") (pinfunction "MH1_MH1") (pintype "passive+no_connect"))
    )
    (net (code "96") (name "unconnected-(MECH7-PadMH1)") (class "Default")
      (node (ref "MECH7") (pin "MH1") (pinfunction "MH1_MH1") (pintype "passive+no_connect"))
    )
    (net (code "97") (name "unconnected-(MECH8-PadMH1)") (class "Default")
      (node (ref "MECH8") (pin "MH1") (pinfunction "MH1_MH1") (pintype "passive+no_connect"))
    )
    (net (code "98") (name "unconnected-(MECH9-PadMH1)") (class "Default")
      (node (ref "MECH9") (pin "MH1") (pinfunction "MH1_MH1") (pintype "passive+no_connect"))
    )
    (net (code "99") (name "unconnected-(MECH10-PadMH1)") (class "Default")
      (node (ref "MECH10") (pin "MH1") (pinfunction "MH1_MH1") (pintype "passive+no_connect"))
    )
    (net (code "100") (name "unconnected-(MECH11-PadMH1)") (class "Default")
      (node (ref "MECH11") (pin "MH1") (pinfunction "MH1_MH1") (pintype "passive+no_connect"))
    )
    (net (code "101") (name "unconnected-(MECH12-PadMH1)") (class "Default")
      (node (ref "MECH12") (pin "MH1") (pinfunction "MH1_MH1") (pintype "passive+no_connect"))
    )
    (net (code "102") (name "unconnected-(MECH13-PadMH1)") (class "Default")
      (node (ref "MECH13") (pin "MH1") (pinfunction "MH1_MH1") (pintype "passive+no_connect"))
    )
    (net (code "103") (name "unconnected-(MECH20-PadMH1)") (class "Default")
      (node (ref "MECH20") (pin "MH1") (pinfunction "MH1_MH1") (pintype "passive+no_connect"))
    )
    (net (code "104") (name "unconnected-(MECH21-PadMH1)") (class "Default")
      (node (ref "MECH21") (pin "MH1") (pinfunction "MH1_MH1") (pintype "passive+no_connect"))
    )
    (net (code "105") (name "unconnected-(MECH22-PadMH1)") (class "Default")
      (node (ref "MECH22") (pin "MH1") (pinfunction "MH1_MH1") (pintype "passive+no_connect"))
    )
    (net (code "106") (name "unconnected-(MECH23-PadMH1)") (class "Default")
      (node (ref "MECH23") (pin "MH1") (pinfunction "MH1_MH1") (pintype "passive+no_connect"))
    )
    (net (code "107") (name "unconnected-(MECH24-PadMH1)") (class "Default")
      (node (ref "MECH24") (pin "MH1") (pinfunction "MH1_MH1") (pintype "passive+no_connect"))
    )
    (net (code "108") (name "unconnected-(MECH25-PadMH1)") (class "Default")
      (node (ref "MECH25") (pin "MH1") (pinfunction "MH1_MH1") (pintype "passive+no_connect"))
    )
    (net (code "109") (name "unconnected-(MECH26-PadMH1)") (class "Default")
      (node (ref "MECH26") (pin "MH1") (pinfunction "MH1_MH1") (pintype "passive+no_connect"))
    )
    (net (code "110") (name "unconnected-(MECH27-PadMH1)") (class "Default")
      (node (ref "MECH27") (pin "MH1") (pinfunction "MH1_MH1") (pintype "passive+no_connect"))
    )
    (net (code "111") (name "unconnected-(MECH28-PadMH1)") (class "Default")
      (node (ref "MECH28") (pin "MH1") (pinfunction "MH1_MH1") (pintype "passive+no_connect"))
    )
  )
)
